# Big-pixel-display-shield.net
KiCad netlist of a schematic drawn in EAGLE
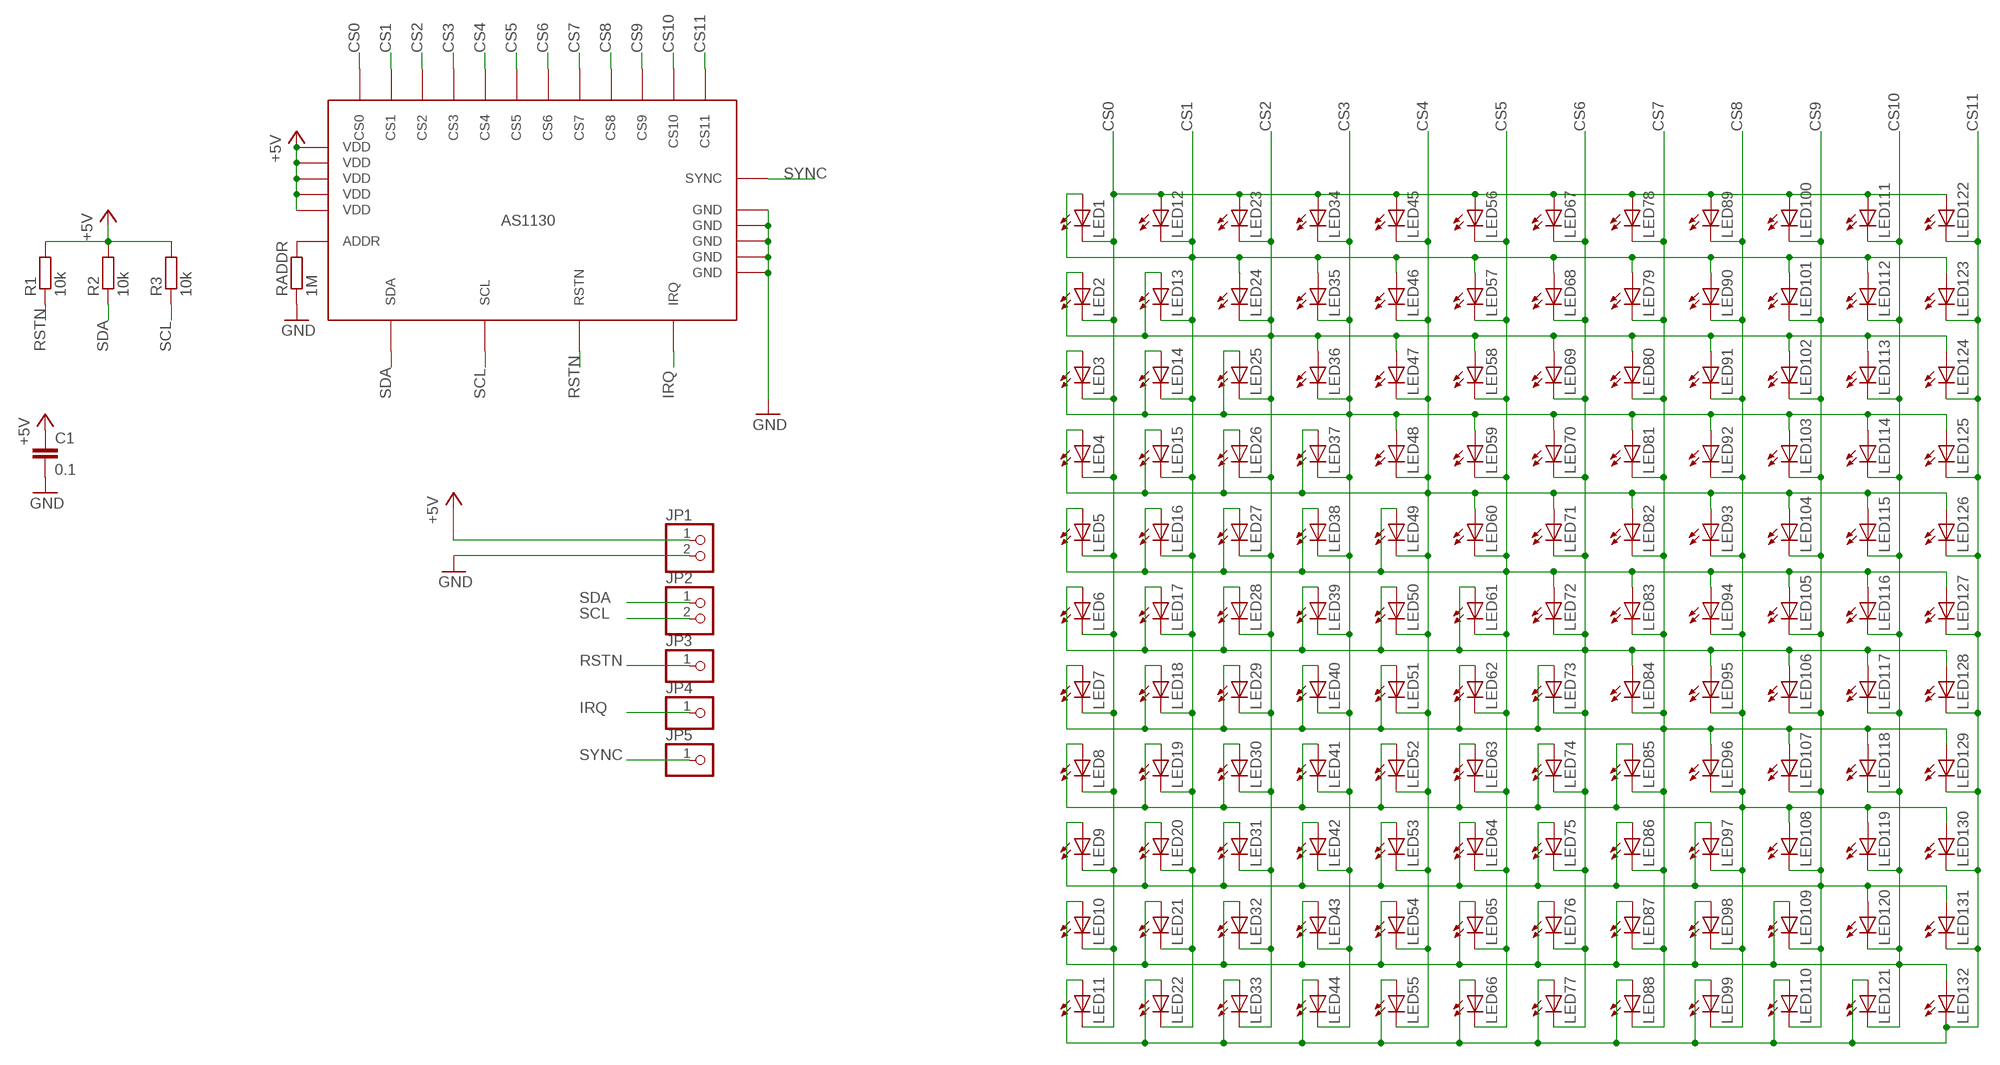
[diagram p0: schematic, sheet 1]

(export (version "E")
  (design (tool "Eeschema 10.0.6"))
  (components
    (comp (ref "C1")
      (value "0.1")
      (footprint "eagle-import:C0805")
      (libsource (lib "eagle-import") (part "C-EUC0805"))
    )
    (comp (ref "JP1")
      (value "PINHD-1X2")
      (footprint "eagle-import:1X02")
      (libsource (lib "eagle-import") (part "PINHD-1X2"))
    )
    (comp (ref "JP2")
      (value "PINHD-1X2")
      (footprint "eagle-import:1X02")
      (libsource (lib "eagle-import") (part "PINHD-1X2"))
    )
    (comp (ref "JP3")
      (value "PINHD-1X1")
      (footprint "eagle-import:1X01")
      (libsource (lib "eagle-import") (part "PINHD-1X1"))
    )
    (comp (ref "JP4")
      (value "PINHD-1X1")
      (footprint "eagle-import:1X01")
      (libsource (lib "eagle-import") (part "PINHD-1X1"))
    )
    (comp (ref "JP5")
      (value "PINHD-1X1")
      (footprint "eagle-import:1X01")
      (libsource (lib "eagle-import") (part "PINHD-1X1"))
    )
    (comp (ref "LED1")
      (value "LED5MM")
      (footprint "eagle-import:LED5MM")
      (libsource (lib "eagle-import") (part "LED5MM"))
    )
    (comp (ref "LED2")
      (value "LED5MM")
      (footprint "eagle-import:LED5MM")
      (libsource (lib "eagle-import") (part "LED5MM"))
    )
    (comp (ref "LED3")
      (value "LED5MM")
      (footprint "eagle-import:LED5MM")
      (libsource (lib "eagle-import") (part "LED5MM"))
    )
    (comp (ref "LED4")
      (value "LED5MM")
      (footprint "eagle-import:LED5MM")
      (libsource (lib "eagle-import") (part "LED5MM"))
    )
    (comp (ref "LED5")
      (value "LED5MM")
      (footprint "eagle-import:LED5MM")
      (libsource (lib "eagle-import") (part "LED5MM"))
    )
    (comp (ref "LED6")
      (value "LED5MM")
      (footprint "eagle-import:LED5MM")
      (libsource (lib "eagle-import") (part "LED5MM"))
    )
    (comp (ref "LED7")
      (value "LED5MM")
      (footprint "eagle-import:LED5MM")
      (libsource (lib "eagle-import") (part "LED5MM"))
    )
    (comp (ref "LED8")
      (value "LED5MM")
      (footprint "eagle-import:LED5MM")
      (libsource (lib "eagle-import") (part "LED5MM"))
    )
    (comp (ref "LED9")
      (value "LED5MM")
      (footprint "eagle-import:LED5MM")
      (libsource (lib "eagle-import") (part "LED5MM"))
    )
    (comp (ref "LED10")
      (value "LED5MM")
      (footprint "eagle-import:LED5MM")
      (libsource (lib "eagle-import") (part "LED5MM"))
    )
    (comp (ref "LED11")
      (value "LED5MM")
      (footprint "eagle-import:LED5MM")
      (libsource (lib "eagle-import") (part "LED5MM"))
    )
    (comp (ref "LED12")
      (value "LED5MM")
      (footprint "eagle-import:LED5MM")
      (libsource (lib "eagle-import") (part "LED5MM"))
    )
    (comp (ref "LED13")
      (value "LED5MM")
      (footprint "eagle-import:LED5MM")
      (libsource (lib "eagle-import") (part "LED5MM"))
    )
    (comp (ref "LED14")
      (value "LED5MM")
      (footprint "eagle-import:LED5MM")
      (libsource (lib "eagle-import") (part "LED5MM"))
    )
    (comp (ref "LED15")
      (value "LED5MM")
      (footprint "eagle-import:LED5MM")
      (libsource (lib "eagle-import") (part "LED5MM"))
    )
    (comp (ref "LED16")
      (value "LED5MM")
      (footprint "eagle-import:LED5MM")
      (libsource (lib "eagle-import") (part "LED5MM"))
    )
    (comp (ref "LED17")
      (value "LED5MM")
      (footprint "eagle-import:LED5MM")
      (libsource (lib "eagle-import") (part "LED5MM"))
    )
    (comp (ref "LED18")
      (value "LED5MM")
      (footprint "eagle-import:LED5MM")
      (libsource (lib "eagle-import") (part "LED5MM"))
    )
    (comp (ref "LED19")
      (value "LED5MM")
      (footprint "eagle-import:LED5MM")
      (libsource (lib "eagle-import") (part "LED5MM"))
    )
    (comp (ref "LED20")
      (value "LED5MM")
      (footprint "eagle-import:LED5MM")
      (libsource (lib "eagle-import") (part "LED5MM"))
    )
    (comp (ref "LED21")
      (value "LED5MM")
      (footprint "eagle-import:LED5MM")
      (libsource (lib "eagle-import") (part "LED5MM"))
    )
    (comp (ref "LED22")
      (value "LED5MM")
      (footprint "eagle-import:LED5MM")
      (libsource (lib "eagle-import") (part "LED5MM"))
    )
    (comp (ref "LED23")
      (value "LED5MM")
      (footprint "eagle-import:LED5MM")
      (libsource (lib "eagle-import") (part "LED5MM"))
    )
    (comp (ref "LED24")
      (value "LED5MM")
      (footprint "eagle-import:LED5MM")
      (libsource (lib "eagle-import") (part "LED5MM"))
    )
    (comp (ref "LED25")
      (value "LED5MM")
      (footprint "eagle-import:LED5MM")
      (libsource (lib "eagle-import") (part "LED5MM"))
    )
    (comp (ref "LED26")
      (value "LED5MM")
      (footprint "eagle-import:LED5MM")
      (libsource (lib "eagle-import") (part "LED5MM"))
    )
    (comp (ref "LED27")
      (value "LED5MM")
      (footprint "eagle-import:LED5MM")
      (libsource (lib "eagle-import") (part "LED5MM"))
    )
    (comp (ref "LED28")
      (value "LED5MM")
      (footprint "eagle-import:LED5MM")
      (libsource (lib "eagle-import") (part "LED5MM"))
    )
    (comp (ref "LED29")
      (value "LED5MM")
      (footprint "eagle-import:LED5MM")
      (libsource (lib "eagle-import") (part "LED5MM"))
    )
    (comp (ref "LED30")
      (value "LED5MM")
      (footprint "eagle-import:LED5MM")
      (libsource (lib "eagle-import") (part "LED5MM"))
    )
    (comp (ref "LED31")
      (value "LED5MM")
      (footprint "eagle-import:LED5MM")
      (libsource (lib "eagle-import") (part "LED5MM"))
    )
    (comp (ref "LED32")
      (value "LED5MM")
      (footprint "eagle-import:LED5MM")
      (libsource (lib "eagle-import") (part "LED5MM"))
    )
    (comp (ref "LED33")
      (value "LED5MM")
      (footprint "eagle-import:LED5MM")
      (libsource (lib "eagle-import") (part "LED5MM"))
    )
    (comp (ref "LED34")
      (value "LED5MM")
      (footprint "eagle-import:LED5MM")
      (libsource (lib "eagle-import") (part "LED5MM"))
    )
    (comp (ref "LED35")
      (value "LED5MM")
      (footprint "eagle-import:LED5MM")
      (libsource (lib "eagle-import") (part "LED5MM"))
    )
    (comp (ref "LED36")
      (value "LED5MM")
      (footprint "eagle-import:LED5MM")
      (libsource (lib "eagle-import") (part "LED5MM"))
    )
    (comp (ref "LED37")
      (value "LED5MM")
      (footprint "eagle-import:LED5MM")
      (libsource (lib "eagle-import") (part "LED5MM"))
    )
    (comp (ref "LED38")
      (value "LED5MM")
      (footprint "eagle-import:LED5MM")
      (libsource (lib "eagle-import") (part "LED5MM"))
    )
    (comp (ref "LED39")
      (value "LED5MM")
      (footprint "eagle-import:LED5MM")
      (libsource (lib "eagle-import") (part "LED5MM"))
    )
    (comp (ref "LED40")
      (value "LED5MM")
      (footprint "eagle-import:LED5MM")
      (libsource (lib "eagle-import") (part "LED5MM"))
    )
    (comp (ref "LED41")
      (value "LED5MM")
      (footprint "eagle-import:LED5MM")
      (libsource (lib "eagle-import") (part "LED5MM"))
    )
    (comp (ref "LED42")
      (value "LED5MM")
      (footprint "eagle-import:LED5MM")
      (libsource (lib "eagle-import") (part "LED5MM"))
    )
    (comp (ref "LED43")
      (value "LED5MM")
      (footprint "eagle-import:LED5MM")
      (libsource (lib "eagle-import") (part "LED5MM"))
    )
    (comp (ref "LED44")
      (value "LED5MM")
      (footprint "eagle-import:LED5MM")
      (libsource (lib "eagle-import") (part "LED5MM"))
    )
    (comp (ref "LED45")
      (value "LED5MM")
      (footprint "eagle-import:LED5MM")
      (libsource (lib "eagle-import") (part "LED5MM"))
    )
    (comp (ref "LED46")
      (value "LED5MM")
      (footprint "eagle-import:LED5MM")
      (libsource (lib "eagle-import") (part "LED5MM"))
    )
    (comp (ref "LED47")
      (value "LED5MM")
      (footprint "eagle-import:LED5MM")
      (libsource (lib "eagle-import") (part "LED5MM"))
    )
    (comp (ref "LED48")
      (value "LED5MM")
      (footprint "eagle-import:LED5MM")
      (libsource (lib "eagle-import") (part "LED5MM"))
    )
    (comp (ref "LED49")
      (value "LED5MM")
      (footprint "eagle-import:LED5MM")
      (libsource (lib "eagle-import") (part "LED5MM"))
    )
    (comp (ref "LED50")
      (value "LED5MM")
      (footprint "eagle-import:LED5MM")
      (libsource (lib "eagle-import") (part "LED5MM"))
    )
    (comp (ref "LED51")
      (value "LED5MM")
      (footprint "eagle-import:LED5MM")
      (libsource (lib "eagle-import") (part "LED5MM"))
    )
    (comp (ref "LED52")
      (value "LED5MM")
      (footprint "eagle-import:LED5MM")
      (libsource (lib "eagle-import") (part "LED5MM"))
    )
    (comp (ref "LED53")
      (value "LED5MM")
      (footprint "eagle-import:LED5MM")
      (libsource (lib "eagle-import") (part "LED5MM"))
    )
    (comp (ref "LED54")
      (value "LED5MM")
      (footprint "eagle-import:LED5MM")
      (libsource (lib "eagle-import") (part "LED5MM"))
    )
    (comp (ref "LED55")
      (value "LED5MM")
      (footprint "eagle-import:LED5MM")
      (libsource (lib "eagle-import") (part "LED5MM"))
    )
    (comp (ref "LED56")
      (value "LED5MM")
      (footprint "eagle-import:LED5MM")
      (libsource (lib "eagle-import") (part "LED5MM"))
    )
    (comp (ref "LED57")
      (value "LED5MM")
      (footprint "eagle-import:LED5MM")
      (libsource (lib "eagle-import") (part "LED5MM"))
    )
    (comp (ref "LED58")
      (value "LED5MM")
      (footprint "eagle-import:LED5MM")
      (libsource (lib "eagle-import") (part "LED5MM"))
    )
    (comp (ref "LED59")
      (value "LED5MM")
      (footprint "eagle-import:LED5MM")
      (libsource (lib "eagle-import") (part "LED5MM"))
    )
    (comp (ref "LED60")
      (value "LED5MM")
      (footprint "eagle-import:LED5MM")
      (libsource (lib "eagle-import") (part "LED5MM"))
    )
    (comp (ref "LED61")
      (value "LED5MM")
      (footprint "eagle-import:LED5MM")
      (libsource (lib "eagle-import") (part "LED5MM"))
    )
    (comp (ref "LED62")
      (value "LED5MM")
      (footprint "eagle-import:LED5MM")
      (libsource (lib "eagle-import") (part "LED5MM"))
    )
    (comp (ref "LED63")
      (value "LED5MM")
      (footprint "eagle-import:LED5MM")
      (libsource (lib "eagle-import") (part "LED5MM"))
    )
    (comp (ref "LED64")
      (value "LED5MM")
      (footprint "eagle-import:LED5MM")
      (libsource (lib "eagle-import") (part "LED5MM"))
    )
    (comp (ref "LED65")
      (value "LED5MM")
      (footprint "eagle-import:LED5MM")
      (libsource (lib "eagle-import") (part "LED5MM"))
    )
    (comp (ref "LED66")
      (value "LED5MM")
      (footprint "eagle-import:LED5MM")
      (libsource (lib "eagle-import") (part "LED5MM"))
    )
    (comp (ref "LED67")
      (value "LED5MM")
      (footprint "eagle-import:LED5MM")
      (libsource (lib "eagle-import") (part "LED5MM"))
    )
    (comp (ref "LED68")
      (value "LED5MM")
      (footprint "eagle-import:LED5MM")
      (libsource (lib "eagle-import") (part "LED5MM"))
    )
    (comp (ref "LED69")
      (value "LED5MM")
      (footprint "eagle-import:LED5MM")
      (libsource (lib "eagle-import") (part "LED5MM"))
    )
    (comp (ref "LED70")
      (value "LED5MM")
      (footprint "eagle-import:LED5MM")
      (libsource (lib "eagle-import") (part "LED5MM"))
    )
    (comp (ref "LED71")
      (value "LED5MM")
      (footprint "eagle-import:LED5MM")
      (libsource (lib "eagle-import") (part "LED5MM"))
    )
    (comp (ref "LED72")
      (value "LED5MM")
      (footprint "eagle-import:LED5MM")
      (libsource (lib "eagle-import") (part "LED5MM"))
    )
    (comp (ref "LED73")
      (value "LED5MM")
      (footprint "eagle-import:LED5MM")
      (libsource (lib "eagle-import") (part "LED5MM"))
    )
    (comp (ref "LED74")
      (value "LED5MM")
      (footprint "eagle-import:LED5MM")
      (libsource (lib "eagle-import") (part "LED5MM"))
    )
    (comp (ref "LED75")
      (value "LED5MM")
      (footprint "eagle-import:LED5MM")
      (libsource (lib "eagle-import") (part "LED5MM"))
    )
    (comp (ref "LED76")
      (value "LED5MM")
      (footprint "eagle-import:LED5MM")
      (libsource (lib "eagle-import") (part "LED5MM"))
    )
    (comp (ref "LED77")
      (value "LED5MM")
      (footprint "eagle-import:LED5MM")
      (libsource (lib "eagle-import") (part "LED5MM"))
    )
    (comp (ref "LED78")
      (value "LED5MM")
      (footprint "eagle-import:LED5MM")
      (libsource (lib "eagle-import") (part "LED5MM"))
    )
    (comp (ref "LED79")
      (value "LED5MM")
      (footprint "eagle-import:LED5MM")
      (libsource (lib "eagle-import") (part "LED5MM"))
    )
    (comp (ref "LED80")
      (value "LED5MM")
      (footprint "eagle-import:LED5MM")
      (libsource (lib "eagle-import") (part "LED5MM"))
    )
    (comp (ref "LED81")
      (value "LED5MM")
      (footprint "eagle-import:LED5MM")
      (libsource (lib "eagle-import") (part "LED5MM"))
    )
    (comp (ref "LED82")
      (value "LED5MM")
      (footprint "eagle-import:LED5MM")
      (libsource (lib "eagle-import") (part "LED5MM"))
    )
    (comp (ref "LED83")
      (value "LED5MM")
      (footprint "eagle-import:LED5MM")
      (libsource (lib "eagle-import") (part "LED5MM"))
    )
    (comp (ref "LED84")
      (value "LED5MM")
      (footprint "eagle-import:LED5MM")
      (libsource (lib "eagle-import") (part "LED5MM"))
    )
    (comp (ref "LED85")
      (value "LED5MM")
      (footprint "eagle-import:LED5MM")
      (libsource (lib "eagle-import") (part "LED5MM"))
    )
    (comp (ref "LED86")
      (value "LED5MM")
      (footprint "eagle-import:LED5MM")
      (libsource (lib "eagle-import") (part "LED5MM"))
    )
    (comp (ref "LED87")
      (value "LED5MM")
      (footprint "eagle-import:LED5MM")
      (libsource (lib "eagle-import") (part "LED5MM"))
    )
    (comp (ref "LED88")
      (value "LED5MM")
      (footprint "eagle-import:LED5MM")
      (libsource (lib "eagle-import") (part "LED5MM"))
    )
    (comp (ref "LED89")
      (value "LED5MM")
      (footprint "eagle-import:LED5MM")
      (libsource (lib "eagle-import") (part "LED5MM"))
    )
    (comp (ref "LED90")
      (value "LED5MM")
      (footprint "eagle-import:LED5MM")
      (libsource (lib "eagle-import") (part "LED5MM"))
    )
    (comp (ref "LED91")
      (value "LED5MM")
      (footprint "eagle-import:LED5MM")
      (libsource (lib "eagle-import") (part "LED5MM"))
    )
    (comp (ref "LED92")
      (value "LED5MM")
      (footprint "eagle-import:LED5MM")
      (libsource (lib "eagle-import") (part "LED5MM"))
    )
    (comp (ref "LED93")
      (value "LED5MM")
      (footprint "eagle-import:LED5MM")
      (libsource (lib "eagle-import") (part "LED5MM"))
    )
    (comp (ref "LED94")
      (value "LED5MM")
      (footprint "eagle-import:LED5MM")
      (libsource (lib "eagle-import") (part "LED5MM"))
    )
    (comp (ref "LED95")
      (value "LED5MM")
      (footprint "eagle-import:LED5MM")
      (libsource (lib "eagle-import") (part "LED5MM"))
    )
    (comp (ref "LED96")
      (value "LED5MM")
      (footprint "eagle-import:LED5MM")
      (libsource (lib "eagle-import") (part "LED5MM"))
    )
    (comp (ref "LED97")
      (value "LED5MM")
      (footprint "eagle-import:LED5MM")
      (libsource (lib "eagle-import") (part "LED5MM"))
    )
    (comp (ref "LED98")
      (value "LED5MM")
      (footprint "eagle-import:LED5MM")
      (libsource (lib "eagle-import") (part "LED5MM"))
    )
    (comp (ref "LED99")
      (value "LED5MM")
      (footprint "eagle-import:LED5MM")
      (libsource (lib "eagle-import") (part "LED5MM"))
    )
    (comp (ref "LED100")
      (value "LED5MM")
      (footprint "eagle-import:LED5MM")
      (libsource (lib "eagle-import") (part "LED5MM"))
    )
    (comp (ref "LED101")
      (value "LED5MM")
      (footprint "eagle-import:LED5MM")
      (libsource (lib "eagle-import") (part "LED5MM"))
    )
    (comp (ref "LED102")
      (value "LED5MM")
      (footprint "eagle-import:LED5MM")
      (libsource (lib "eagle-import") (part "LED5MM"))
    )
    (comp (ref "LED103")
      (value "LED5MM")
      (footprint "eagle-import:LED5MM")
      (libsource (lib "eagle-import") (part "LED5MM"))
    )
    (comp (ref "LED104")
      (value "LED5MM")
      (footprint "eagle-import:LED5MM")
      (libsource (lib "eagle-import") (part "LED5MM"))
    )
    (comp (ref "LED105")
      (value "LED5MM")
      (footprint "eagle-import:LED5MM")
      (libsource (lib "eagle-import") (part "LED5MM"))
    )
    (comp (ref "LED106")
      (value "LED5MM")
      (footprint "eagle-import:LED5MM")
      (libsource (lib "eagle-import") (part "LED5MM"))
    )
    (comp (ref "LED107")
      (value "LED5MM")
      (footprint "eagle-import:LED5MM")
      (libsource (lib "eagle-import") (part "LED5MM"))
    )
    (comp (ref "LED108")
      (value "LED5MM")
      (footprint "eagle-import:LED5MM")
      (libsource (lib "eagle-import") (part "LED5MM"))
    )
    (comp (ref "LED109")
      (value "LED5MM")
      (footprint "eagle-import:LED5MM")
      (libsource (lib "eagle-import") (part "LED5MM"))
    )
    (comp (ref "LED110")
      (value "LED5MM")
      (footprint "eagle-import:LED5MM")
      (libsource (lib "eagle-import") (part "LED5MM"))
    )
    (comp (ref "LED111")
      (value "LED5MM")
      (footprint "eagle-import:LED5MM")
      (libsource (lib "eagle-import") (part "LED5MM"))
    )
    (comp (ref "LED112")
      (value "LED5MM")
      (footprint "eagle-import:LED5MM")
      (libsource (lib "eagle-import") (part "LED5MM"))
    )
    (comp (ref "LED113")
      (value "LED5MM")
      (footprint "eagle-import:LED5MM")
      (libsource (lib "eagle-import") (part "LED5MM"))
    )
    (comp (ref "LED114")
      (value "LED5MM")
      (footprint "eagle-import:LED5MM")
      (libsource (lib "eagle-import") (part "LED5MM"))
    )
    (comp (ref "LED115")
      (value "LED5MM")
      (footprint "eagle-import:LED5MM")
      (libsource (lib "eagle-import") (part "LED5MM"))
    )
    (comp (ref "LED116")
      (value "LED5MM")
      (footprint "eagle-import:LED5MM")
      (libsource (lib "eagle-import") (part "LED5MM"))
    )
    (comp (ref "LED117")
      (value "LED5MM")
      (footprint "eagle-import:LED5MM")
      (libsource (lib "eagle-import") (part "LED5MM"))
    )
    (comp (ref "LED118")
      (value "LED5MM")
      (footprint "eagle-import:LED5MM")
      (libsource (lib "eagle-import") (part "LED5MM"))
    )
    (comp (ref "LED119")
      (value "LED5MM")
      (footprint "eagle-import:LED5MM")
      (libsource (lib "eagle-import") (part "LED5MM"))
    )
    (comp (ref "LED120")
      (value "LED5MM")
      (footprint "eagle-import:LED5MM")
      (libsource (lib "eagle-import") (part "LED5MM"))
    )
    (comp (ref "LED121")
      (value "LED5MM")
      (footprint "eagle-import:LED5MM")
      (libsource (lib "eagle-import") (part "LED5MM"))
    )
    (comp (ref "LED122")
      (value "LED5MM")
      (footprint "eagle-import:LED5MM")
      (libsource (lib "eagle-import") (part "LED5MM"))
    )
    (comp (ref "LED123")
      (value "LED5MM")
      (footprint "eagle-import:LED5MM")
      (libsource (lib "eagle-import") (part "LED5MM"))
    )
    (comp (ref "LED124")
      (value "LED5MM")
      (footprint "eagle-import:LED5MM")
      (libsource (lib "eagle-import") (part "LED5MM"))
    )
    (comp (ref "LED125")
      (value "LED5MM")
      (footprint "eagle-import:LED5MM")
      (libsource (lib "eagle-import") (part "LED5MM"))
    )
    (comp (ref "LED126")
      (value "LED5MM")
      (footprint "eagle-import:LED5MM")
      (libsource (lib "eagle-import") (part "LED5MM"))
    )
    (comp (ref "LED127")
      (value "LED5MM")
      (footprint "eagle-import:LED5MM")
      (libsource (lib "eagle-import") (part "LED5MM"))
    )
    (comp (ref "LED128")
      (value "LED5MM")
      (footprint "eagle-import:LED5MM")
      (libsource (lib "eagle-import") (part "LED5MM"))
    )
    (comp (ref "LED129")
      (value "LED5MM")
      (footprint "eagle-import:LED5MM")
      (libsource (lib "eagle-import") (part "LED5MM"))
    )
    (comp (ref "LED130")
      (value "LED5MM")
      (footprint "eagle-import:LED5MM")
      (libsource (lib "eagle-import") (part "LED5MM"))
    )
    (comp (ref "LED131")
      (value "LED5MM")
      (footprint "eagle-import:LED5MM")
      (libsource (lib "eagle-import") (part "LED5MM"))
    )
    (comp (ref "LED132")
      (value "LED5MM")
      (footprint "eagle-import:LED5MM")
      (libsource (lib "eagle-import") (part "LED5MM"))
    )
    (comp (ref "R1")
      (value "10k")
      (footprint "eagle-import:R1206")
      (libsource (lib "eagle-import") (part "R-EU_R1206"))
    )
    (comp (ref "R2")
      (value "10k")
      (footprint "eagle-import:R1206")
      (libsource (lib "eagle-import") (part "R-EU_R1206"))
    )
    (comp (ref "R3")
      (value "10k")
      (footprint "eagle-import:R1206")
      (libsource (lib "eagle-import") (part "R-EU_R1206"))
    )
    (comp (ref "RADDR")
      (value "1M")
      (footprint "eagle-import:R1206")
      (libsource (lib "eagle-import") (part "R-EU_R1206"))
    )
    (comp (ref "U$1")
      (value "AS1130")
      (footprint "eagle-import:SSOP28")
      (libsource (lib "eagle-import") (part "AS1130"))
    )
  )
  (nets
    (net (code "1") (name "+5V") (class "Default")
      (node (ref "C1") (pin "1") (pinfunction "1_1") (pintype "passive"))
      (node (ref "JP1") (pin "1") (pinfunction "1_1") (pintype "passive"))
      (node (ref "R1") (pin "2") (pinfunction "2_2") (pintype "passive"))
      (node (ref "R2") (pin "2") (pinfunction "2_2") (pintype "passive"))
      (node (ref "R3") (pin "2") (pinfunction "2_2") (pintype "passive"))
      (node (ref "U$1") (pin "10") (pinfunction "VDD_10") (pintype "bidirectional"))
      (node (ref "U$1") (pin "18") (pinfunction "VDD_18") (pintype "bidirectional"))
      (node (ref "U$1") (pin "19") (pinfunction "VDD_19") (pintype "bidirectional"))
      (node (ref "U$1") (pin "26") (pinfunction "VDD_26") (pintype "bidirectional"))
      (node (ref "U$1") (pin "3") (pinfunction "VDD_3") (pintype "bidirectional"))
    )
    (net (code "2") (name "/CS0") (class "Default")
      (node (ref "LED1") (pin "K") (pinfunction "C_K") (pintype "passive"))
      (node (ref "LED10") (pin "K") (pinfunction "C_K") (pintype "passive"))
      (node (ref "LED100") (pin "A") (pinfunction "A_A") (pintype "passive"))
      (node (ref "LED11") (pin "K") (pinfunction "C_K") (pintype "passive"))
      (node (ref "LED111") (pin "A") (pinfunction "A_A") (pintype "passive"))
      (node (ref "LED12") (pin "A") (pinfunction "A_A") (pintype "passive"))
      (node (ref "LED122") (pin "A") (pinfunction "A_A") (pintype "passive"))
      (node (ref "LED2") (pin "K") (pinfunction "C_K") (pintype "passive"))
      (node (ref "LED23") (pin "A") (pinfunction "A_A") (pintype "passive"))
      (node (ref "LED3") (pin "K") (pinfunction "C_K") (pintype "passive"))
      (node (ref "LED34") (pin "A") (pinfunction "A_A") (pintype "passive"))
      (node (ref "LED4") (pin "K") (pinfunction "C_K") (pintype "passive"))
      (node (ref "LED45") (pin "A") (pinfunction "A_A") (pintype "passive"))
      (node (ref "LED5") (pin "K") (pinfunction "C_K") (pintype "passive"))
      (node (ref "LED56") (pin "A") (pinfunction "A_A") (pintype "passive"))
      (node (ref "LED6") (pin "K") (pinfunction "C_K") (pintype "passive"))
      (node (ref "LED67") (pin "A") (pinfunction "A_A") (pintype "passive"))
      (node (ref "LED7") (pin "K") (pinfunction "C_K") (pintype "passive"))
      (node (ref "LED78") (pin "A") (pinfunction "A_A") (pintype "passive"))
      (node (ref "LED8") (pin "K") (pinfunction "C_K") (pintype "passive"))
      (node (ref "LED89") (pin "A") (pinfunction "A_A") (pintype "passive"))
      (node (ref "LED9") (pin "K") (pinfunction "C_K") (pintype "passive"))
      (node (ref "U$1") (pin "25") (pinfunction "CS0_25") (pintype "bidirectional"))
    )
    (net (code "3") (name "/CS1") (class "Default")
      (node (ref "LED1") (pin "A") (pinfunction "A_A") (pintype "passive"))
      (node (ref "LED101") (pin "A") (pinfunction "A_A") (pintype "passive"))
      (node (ref "LED112") (pin "A") (pinfunction "A_A") (pintype "passive"))
      (node (ref "LED12") (pin "K") (pinfunction "C_K") (pintype "passive"))
      (node (ref "LED123") (pin "A") (pinfunction "A_A") (pintype "passive"))
      (node (ref "LED13") (pin "K") (pinfunction "C_K") (pintype "passive"))
      (node (ref "LED14") (pin "K") (pinfunction "C_K") (pintype "passive"))
      (node (ref "LED15") (pin "K") (pinfunction "C_K") (pintype "passive"))
      (node (ref "LED16") (pin "K") (pinfunction "C_K") (pintype "passive"))
      (node (ref "LED17") (pin "K") (pinfunction "C_K") (pintype "passive"))
      (node (ref "LED18") (pin "K") (pinfunction "C_K") (pintype "passive"))
      (node (ref "LED19") (pin "K") (pinfunction "C_K") (pintype "passive"))
      (node (ref "LED20") (pin "K") (pinfunction "C_K") (pintype "passive"))
      (node (ref "LED21") (pin "K") (pinfunction "C_K") (pintype "passive"))
      (node (ref "LED22") (pin "K") (pinfunction "C_K") (pintype "passive"))
      (node (ref "LED24") (pin "A") (pinfunction "A_A") (pintype "passive"))
      (node (ref "LED35") (pin "A") (pinfunction "A_A") (pintype "passive"))
      (node (ref "LED46") (pin "A") (pinfunction "A_A") (pintype "passive"))
      (node (ref "LED57") (pin "A") (pinfunction "A_A") (pintype "passive"))
      (node (ref "LED68") (pin "A") (pinfunction "A_A") (pintype "passive"))
      (node (ref "LED79") (pin "A") (pinfunction "A_A") (pintype "passive"))
      (node (ref "LED90") (pin "A") (pinfunction "A_A") (pintype "passive"))
      (node (ref "U$1") (pin "27") (pinfunction "CS1_27") (pintype "bidirectional"))
    )
    (net (code "4") (name "/CS2") (class "Default")
      (node (ref "LED102") (pin "A") (pinfunction "A_A") (pintype "passive"))
      (node (ref "LED113") (pin "A") (pinfunction "A_A") (pintype "passive"))
      (node (ref "LED124") (pin "A") (pinfunction "A_A") (pintype "passive"))
      (node (ref "LED13") (pin "A") (pinfunction "A_A") (pintype "passive"))
      (node (ref "LED2") (pin "A") (pinfunction "A_A") (pintype "passive"))
      (node (ref "LED23") (pin "K") (pinfunction "C_K") (pintype "passive"))
      (node (ref "LED24") (pin "K") (pinfunction "C_K") (pintype "passive"))
      (node (ref "LED25") (pin "K") (pinfunction "C_K") (pintype "passive"))
      (node (ref "LED26") (pin "K") (pinfunction "C_K") (pintype "passive"))
      (node (ref "LED27") (pin "K") (pinfunction "C_K") (pintype "passive"))
      (node (ref "LED28") (pin "K") (pinfunction "C_K") (pintype "passive"))
      (node (ref "LED29") (pin "K") (pinfunction "C_K") (pintype "passive"))
      (node (ref "LED30") (pin "K") (pinfunction "C_K") (pintype "passive"))
      (node (ref "LED31") (pin "K") (pinfunction "C_K") (pintype "passive"))
      (node (ref "LED32") (pin "K") (pinfunction "C_K") (pintype "passive"))
      (node (ref "LED33") (pin "K") (pinfunction "C_K") (pintype "passive"))
      (node (ref "LED36") (pin "A") (pinfunction "A_A") (pintype "passive"))
      (node (ref "LED47") (pin "A") (pinfunction "A_A") (pintype "passive"))
      (node (ref "LED58") (pin "A") (pinfunction "A_A") (pintype "passive"))
      (node (ref "LED69") (pin "A") (pinfunction "A_A") (pintype "passive"))
      (node (ref "LED80") (pin "A") (pinfunction "A_A") (pintype "passive"))
      (node (ref "LED91") (pin "A") (pinfunction "A_A") (pintype "passive"))
      (node (ref "U$1") (pin "23") (pinfunction "CS2_23") (pintype "bidirectional"))
    )
    (net (code "5") (name "/CS3") (class "Default")
      (node (ref "LED103") (pin "A") (pinfunction "A_A") (pintype "passive"))
      (node (ref "LED114") (pin "A") (pinfunction "A_A") (pintype "passive"))
      (node (ref "LED125") (pin "A") (pinfunction "A_A") (pintype "passive"))
      (node (ref "LED14") (pin "A") (pinfunction "A_A") (pintype "passive"))
      (node (ref "LED25") (pin "A") (pinfunction "A_A") (pintype "passive"))
      (node (ref "LED3") (pin "A") (pinfunction "A_A") (pintype "passive"))
      (node (ref "LED34") (pin "K") (pinfunction "C_K") (pintype "passive"))
      (node (ref "LED35") (pin "K") (pinfunction "C_K") (pintype "passive"))
      (node (ref "LED36") (pin "K") (pinfunction "C_K") (pintype "passive"))
      (node (ref "LED37") (pin "K") (pinfunction "C_K") (pintype "passive"))
      (node (ref "LED38") (pin "K") (pinfunction "C_K") (pintype "passive"))
      (node (ref "LED39") (pin "K") (pinfunction "C_K") (pintype "passive"))
      (node (ref "LED40") (pin "K") (pinfunction "C_K") (pintype "passive"))
      (node (ref "LED41") (pin "K") (pinfunction "C_K") (pintype "passive"))
      (node (ref "LED42") (pin "K") (pinfunction "C_K") (pintype "passive"))
      (node (ref "LED43") (pin "K") (pinfunction "C_K") (pintype "passive"))
      (node (ref "LED44") (pin "K") (pinfunction "C_K") (pintype "passive"))
      (node (ref "LED48") (pin "A") (pinfunction "A_A") (pintype "passive"))
      (node (ref "LED59") (pin "A") (pinfunction "A_A") (pintype "passive"))
      (node (ref "LED70") (pin "A") (pinfunction "A_A") (pintype "passive"))
      (node (ref "LED81") (pin "A") (pinfunction "A_A") (pintype "passive"))
      (node (ref "LED92") (pin "A") (pinfunction "A_A") (pintype "passive"))
      (node (ref "U$1") (pin "24") (pinfunction "CS3_24") (pintype "bidirectional"))
    )
    (net (code "6") (name "/CS4") (class "Default")
      (node (ref "LED104") (pin "A") (pinfunction "A_A") (pintype "passive"))
      (node (ref "LED115") (pin "A") (pinfunction "A_A") (pintype "passive"))
      (node (ref "LED126") (pin "A") (pinfunction "A_A") (pintype "passive"))
      (node (ref "LED15") (pin "A") (pinfunction "A_A") (pintype "passive"))
      (node (ref "LED26") (pin "A") (pinfunction "A_A") (pintype "passive"))
      (node (ref "LED37") (pin "A") (pinfunction "A_A") (pintype "passive"))
      (node (ref "LED4") (pin "A") (pinfunction "A_A") (pintype "passive"))
      (node (ref "LED45") (pin "K") (pinfunction "C_K") (pintype "passive"))
      (node (ref "LED46") (pin "K") (pinfunction "C_K") (pintype "passive"))
      (node (ref "LED47") (pin "K") (pinfunction "C_K") (pintype "passive"))
      (node (ref "LED48") (pin "K") (pinfunction "C_K") (pintype "passive"))
      (node (ref "LED49") (pin "K") (pinfunction "C_K") (pintype "passive"))
      (node (ref "LED50") (pin "K") (pinfunction "C_K") (pintype "passive"))
      (node (ref "LED51") (pin "K") (pinfunction "C_K") (pintype "passive"))
      (node (ref "LED52") (pin "K") (pinfunction "C_K") (pintype "passive"))
      (node (ref "LED53") (pin "K") (pinfunction "C_K") (pintype "passive"))
      (node (ref "LED54") (pin "K") (pinfunction "C_K") (pintype "passive"))
      (node (ref "LED55") (pin "K") (pinfunction "C_K") (pintype "passive"))
      (node (ref "LED60") (pin "A") (pinfunction "A_A") (pintype "passive"))
      (node (ref "LED71") (pin "A") (pinfunction "A_A") (pintype "passive"))
      (node (ref "LED82") (pin "A") (pinfunction "A_A") (pintype "passive"))
      (node (ref "LED93") (pin "A") (pinfunction "A_A") (pintype "passive"))
      (node (ref "U$1") (pin "21") (pinfunction "CS4_21") (pintype "bidirectional"))
    )
    (net (code "7") (name "/CS5") (class "Default")
      (node (ref "LED105") (pin "A") (pinfunction "A_A") (pintype "passive"))
      (node (ref "LED116") (pin "A") (pinfunction "A_A") (pintype "passive"))
      (node (ref "LED127") (pin "A") (pinfunction "A_A") (pintype "passive"))
      (node (ref "LED16") (pin "A") (pinfunction "A_A") (pintype "passive"))
      (node (ref "LED27") (pin "A") (pinfunction "A_A") (pintype "passive"))
      (node (ref "LED38") (pin "A") (pinfunction "A_A") (pintype "passive"))
      (node (ref "LED49") (pin "A") (pinfunction "A_A") (pintype "passive"))
      (node (ref "LED5") (pin "A") (pinfunction "A_A") (pintype "passive"))
      (node (ref "LED56") (pin "K") (pinfunction "C_K") (pintype "passive"))
      (node (ref "LED57") (pin "K") (pinfunction "C_K") (pintype "passive"))
      (node (ref "LED58") (pin "K") (pinfunction "C_K") (pintype "passive"))
      (node (ref "LED59") (pin "K") (pinfunction "C_K") (pintype "passive"))
      (node (ref "LED60") (pin "K") (pinfunction "C_K") (pintype "passive"))
      (node (ref "LED61") (pin "K") (pinfunction "C_K") (pintype "passive"))
      (node (ref "LED62") (pin "K") (pinfunction "C_K") (pintype "passive"))
      (node (ref "LED63") (pin "K") (pinfunction "C_K") (pintype "passive"))
      (node (ref "LED64") (pin "K") (pinfunction "C_K") (pintype "passive"))
      (node (ref "LED65") (pin "K") (pinfunction "C_K") (pintype "passive"))
      (node (ref "LED66") (pin "K") (pinfunction "C_K") (pintype "passive"))
      (node (ref "LED72") (pin "A") (pinfunction "A_A") (pintype "passive"))
      (node (ref "LED83") (pin "A") (pinfunction "A_A") (pintype "passive"))
      (node (ref "LED94") (pin "A") (pinfunction "A_A") (pintype "passive"))
      (node (ref "U$1") (pin "20") (pinfunction "CS5_20") (pintype "bidirectional"))
    )
    (net (code "8") (name "/CS6") (class "Default")
      (node (ref "LED106") (pin "A") (pinfunction "A_A") (pintype "passive"))
      (node (ref "LED117") (pin "A") (pinfunction "A_A") (pintype "passive"))
      (node (ref "LED128") (pin "A") (pinfunction "A_A") (pintype "passive"))
      (node (ref "LED17") (pin "A") (pinfunction "A_A") (pintype "passive"))
      (node (ref "LED28") (pin "A") (pinfunction "A_A") (pintype "passive"))
      (node (ref "LED39") (pin "A") (pinfunction "A_A") (pintype "passive"))
      (node (ref "LED50") (pin "A") (pinfunction "A_A") (pintype "passive"))
      (node (ref "LED6") (pin "A") (pinfunction "A_A") (pintype "passive"))
      (node (ref "LED61") (pin "A") (pinfunction "A_A") (pintype "passive"))
      (node (ref "LED67") (pin "K") (pinfunction "C_K") (pintype "passive"))
      (node (ref "LED68") (pin "K") (pinfunction "C_K") (pintype "passive"))
      (node (ref "LED69") (pin "K") (pinfunction "C_K") (pintype "passive"))
      (node (ref "LED70") (pin "K") (pinfunction "C_K") (pintype "passive"))
      (node (ref "LED71") (pin "K") (pinfunction "C_K") (pintype "passive"))
      (node (ref "LED72") (pin "K") (pinfunction "C_K") (pintype "passive"))
      (node (ref "LED73") (pin "K") (pinfunction "C_K") (pintype "passive"))
      (node (ref "LED74") (pin "K") (pinfunction "C_K") (pintype "passive"))
      (node (ref "LED75") (pin "K") (pinfunction "C_K") (pintype "passive"))
      (node (ref "LED76") (pin "K") (pinfunction "C_K") (pintype "passive"))
      (node (ref "LED77") (pin "K") (pinfunction "C_K") (pintype "passive"))
      (node (ref "LED84") (pin "A") (pinfunction "A_A") (pintype "passive"))
      (node (ref "LED95") (pin "A") (pinfunction "A_A") (pintype "passive"))
      (node (ref "U$1") (pin "2") (pinfunction "CS6_2") (pintype "bidirectional"))
    )
    (net (code "9") (name "/CS7") (class "Default")
      (node (ref "LED107") (pin "A") (pinfunction "A_A") (pintype "passive"))
      (node (ref "LED118") (pin "A") (pinfunction "A_A") (pintype "passive"))
      (node (ref "LED129") (pin "A") (pinfunction "A_A") (pintype "passive"))
      (node (ref "LED18") (pin "A") (pinfunction "A_A") (pintype "passive"))
      (node (ref "LED29") (pin "A") (pinfunction "A_A") (pintype "passive"))
      (node (ref "LED40") (pin "A") (pinfunction "A_A") (pintype "passive"))
      (node (ref "LED51") (pin "A") (pinfunction "A_A") (pintype "passive"))
      (node (ref "LED62") (pin "A") (pinfunction "A_A") (pintype "passive"))
      (node (ref "LED7") (pin "A") (pinfunction "A_A") (pintype "passive"))
      (node (ref "LED73") (pin "A") (pinfunction "A_A") (pintype "passive"))
      (node (ref "LED78") (pin "K") (pinfunction "C_K") (pintype "passive"))
      (node (ref "LED79") (pin "K") (pinfunction "C_K") (pintype "passive"))
      (node (ref "LED80") (pin "K") (pinfunction "C_K") (pintype "passive"))
      (node (ref "LED81") (pin "K") (pinfunction "C_K") (pintype "passive"))
      (node (ref "LED82") (pin "K") (pinfunction "C_K") (pintype "passive"))
      (node (ref "LED83") (pin "K") (pinfunction "C_K") (pintype "passive"))
      (node (ref "LED84") (pin "K") (pinfunction "C_K") (pintype "passive"))
      (node (ref "LED85") (pin "K") (pinfunction "C_K") (pintype "passive"))
      (node (ref "LED86") (pin "K") (pinfunction "C_K") (pintype "passive"))
      (node (ref "LED87") (pin "K") (pinfunction "C_K") (pintype "passive"))
      (node (ref "LED88") (pin "K") (pinfunction "C_K") (pintype "passive"))
      (node (ref "LED96") (pin "A") (pinfunction "A_A") (pintype "passive"))
      (node (ref "U$1") (pin "4") (pinfunction "CS7_4") (pintype "bidirectional"))
    )
    (net (code "10") (name "/CS8") (class "Default")
      (node (ref "LED108") (pin "A") (pinfunction "A_A") (pintype "passive"))
      (node (ref "LED119") (pin "A") (pinfunction "A_A") (pintype "passive"))
      (node (ref "LED130") (pin "A") (pinfunction "A_A") (pintype "passive"))
      (node (ref "LED19") (pin "A") (pinfunction "A_A") (pintype "passive"))
      (node (ref "LED30") (pin "A") (pinfunction "A_A") (pintype "passive"))
      (node (ref "LED41") (pin "A") (pinfunction "A_A") (pintype "passive"))
      (node (ref "LED52") (pin "A") (pinfunction "A_A") (pintype "passive"))
      (node (ref "LED63") (pin "A") (pinfunction "A_A") (pintype "passive"))
      (node (ref "LED74") (pin "A") (pinfunction "A_A") (pintype "passive"))
      (node (ref "LED8") (pin "A") (pinfunction "A_A") (pintype "passive"))
      (node (ref "LED85") (pin "A") (pinfunction "A_A") (pintype "passive"))
      (node (ref "LED89") (pin "K") (pinfunction "C_K") (pintype "passive"))
      (node (ref "LED90") (pin "K") (pinfunction "C_K") (pintype "passive"))
      (node (ref "LED91") (pin "K") (pinfunction "C_K") (pintype "passive"))
      (node (ref "LED92") (pin "K") (pinfunction "C_K") (pintype "passive"))
      (node (ref "LED93") (pin "K") (pinfunction "C_K") (pintype "passive"))
      (node (ref "LED94") (pin "K") (pinfunction "C_K") (pintype "passive"))
      (node (ref "LED95") (pin "K") (pinfunction "C_K") (pintype "passive"))
      (node (ref "LED96") (pin "K") (pinfunction "C_K") (pintype "passive"))
      (node (ref "LED97") (pin "K") (pinfunction "C_K") (pintype "passive"))
      (node (ref "LED98") (pin "K") (pinfunction "C_K") (pintype "passive"))
      (node (ref "LED99") (pin "K") (pinfunction "C_K") (pintype "passive"))
      (node (ref "U$1") (pin "5") (pinfunction "CS8_5") (pintype "bidirectional"))
    )
    (net (code "11") (name "/CS9") (class "Default")
      (node (ref "LED100") (pin "K") (pinfunction "C_K") (pintype "passive"))
      (node (ref "LED101") (pin "K") (pinfunction "C_K") (pintype "passive"))
      (node (ref "LED102") (pin "K") (pinfunction "C_K") (pintype "passive"))
      (node (ref "LED103") (pin "K") (pinfunction "C_K") (pintype "passive"))
      (node (ref "LED104") (pin "K") (pinfunction "C_K") (pintype "passive"))
      (node (ref "LED105") (pin "K") (pinfunction "C_K") (pintype "passive"))
      (node (ref "LED106") (pin "K") (pinfunction "C_K") (pintype "passive"))
      (node (ref "LED107") (pin "K") (pinfunction "C_K") (pintype "passive"))
      (node (ref "LED108") (pin "K") (pinfunction "C_K") (pintype "passive"))
      (node (ref "LED109") (pin "K") (pinfunction "C_K") (pintype "passive"))
      (node (ref "LED110") (pin "K") (pinfunction "C_K") (pintype "passive"))
      (node (ref "LED120") (pin "A") (pinfunction "A_A") (pintype "passive"))
      (node (ref "LED131") (pin "A") (pinfunction "A_A") (pintype "passive"))
      (node (ref "LED20") (pin "A") (pinfunction "A_A") (pintype "passive"))
      (node (ref "LED31") (pin "A") (pinfunction "A_A") (pintype "passive"))
      (node (ref "LED42") (pin "A") (pinfunction "A_A") (pintype "passive"))
      (node (ref "LED53") (pin "A") (pinfunction "A_A") (pintype "passive"))
      (node (ref "LED64") (pin "A") (pinfunction "A_A") (pintype "passive"))
      (node (ref "LED75") (pin "A") (pinfunction "A_A") (pintype "passive"))
      (node (ref "LED86") (pin "A") (pinfunction "A_A") (pintype "passive"))
      (node (ref "LED9") (pin "A") (pinfunction "A_A") (pintype "passive"))
      (node (ref "LED97") (pin "A") (pinfunction "A_A") (pintype "passive"))
      (node (ref "U$1") (pin "6") (pinfunction "CS9_6") (pintype "bidirectional"))
    )
    (net (code "12") (name "/CS10") (class "Default")
      (node (ref "LED10") (pin "A") (pinfunction "A_A") (pintype "passive"))
      (node (ref "LED109") (pin "A") (pinfunction "A_A") (pintype "passive"))
      (node (ref "LED111") (pin "K") (pinfunction "C_K") (pintype "passive"))
      (node (ref "LED112") (pin "K") (pinfunction "C_K") (pintype "passive"))
      (node (ref "LED113") (pin "K") (pinfunction "C_K") (pintype "passive"))
      (node (ref "LED114") (pin "K") (pinfunction "C_K") (pintype "passive"))
      (node (ref "LED115") (pin "K") (pinfunction "C_K") (pintype "passive"))
      (node (ref "LED116") (pin "K") (pinfunction "C_K") (pintype "passive"))
      (node (ref "LED117") (pin "K") (pinfunction "C_K") (pintype "passive"))
      (node (ref "LED118") (pin "K") (pinfunction "C_K") (pintype "passive"))
      (node (ref "LED119") (pin "K") (pinfunction "C_K") (pintype "passive"))
      (node (ref "LED120") (pin "K") (pinfunction "C_K") (pintype "passive"))
      (node (ref "LED121") (pin "K") (pinfunction "C_K") (pintype "passive"))
      (node (ref "LED132") (pin "A") (pinfunction "A_A") (pintype "passive"))
      (node (ref "LED21") (pin "A") (pinfunction "A_A") (pintype "passive"))
      (node (ref "LED32") (pin "A") (pinfunction "A_A") (pintype "passive"))
      (node (ref "LED43") (pin "A") (pinfunction "A_A") (pintype "passive"))
      (node (ref "LED54") (pin "A") (pinfunction "A_A") (pintype "passive"))
      (node (ref "LED65") (pin "A") (pinfunction "A_A") (pintype "passive"))
      (node (ref "LED76") (pin "A") (pinfunction "A_A") (pintype "passive"))
      (node (ref "LED87") (pin "A") (pinfunction "A_A") (pintype "passive"))
      (node (ref "LED98") (pin "A") (pinfunction "A_A") (pintype "passive"))
      (node (ref "U$1") (pin "9") (pinfunction "CS10_9") (pintype "bidirectional"))
    )
    (net (code "13") (name "/CS11") (class "Default")
      (node (ref "LED11") (pin "A") (pinfunction "A_A") (pintype "passive"))
      (node (ref "LED110") (pin "A") (pinfunction "A_A") (pintype "passive"))
      (node (ref "LED121") (pin "A") (pinfunction "A_A") (pintype "passive"))
      (node (ref "LED122") (pin "K") (pinfunction "C_K") (pintype "passive"))
      (node (ref "LED123") (pin "K") (pinfunction "C_K") (pintype "passive"))
      (node (ref "LED124") (pin "K") (pinfunction "C_K") (pintype "passive"))
      (node (ref "LED125") (pin "K") (pinfunction "C_K") (pintype "passive"))
      (node (ref "LED126") (pin "K") (pinfunction "C_K") (pintype "passive"))
      (node (ref "LED127") (pin "K") (pinfunction "C_K") (pintype "passive"))
      (node (ref "LED128") (pin "K") (pinfunction "C_K") (pintype "passive"))
      (node (ref "LED129") (pin "K") (pinfunction "C_K") (pintype "passive"))
      (node (ref "LED130") (pin "K") (pinfunction "C_K") (pintype "passive"))
      (node (ref "LED131") (pin "K") (pinfunction "C_K") (pintype "passive"))
      (node (ref "LED132") (pin "K") (pinfunction "C_K") (pintype "passive"))
      (node (ref "LED22") (pin "A") (pinfunction "A_A") (pintype "passive"))
      (node (ref "LED33") (pin "A") (pinfunction "A_A") (pintype "passive"))
      (node (ref "LED44") (pin "A") (pinfunction "A_A") (pintype "passive"))
      (node (ref "LED55") (pin "A") (pinfunction "A_A") (pintype "passive"))
      (node (ref "LED66") (pin "A") (pinfunction "A_A") (pintype "passive"))
      (node (ref "LED77") (pin "A") (pinfunction "A_A") (pintype "passive"))
      (node (ref "LED88") (pin "A") (pinfunction "A_A") (pintype "passive"))
      (node (ref "LED99") (pin "A") (pinfunction "A_A") (pintype "passive"))
      (node (ref "U$1") (pin "8") (pinfunction "CS11_8") (pintype "bidirectional"))
    )
    (net (code "14") (name "/IRQ") (class "Default")
      (node (ref "JP4") (pin "1") (pinfunction "1_1") (pintype "passive"))
      (node (ref "U$1") (pin "11") (pinfunction "IRQ_11") (pintype "bidirectional"))
    )
    (net (code "15") (name "/RSTN") (class "Default")
      (node (ref "JP3") (pin "1") (pinfunction "1_1") (pintype "passive"))
      (node (ref "R1") (pin "1") (pinfunction "1_1") (pintype "passive"))
      (node (ref "U$1") (pin "13") (pinfunction "RSTN_13") (pintype "bidirectional"))
    )
    (net (code "16") (name "/SCL") (class "Default")
      (node (ref "JP2") (pin "2") (pinfunction "2_2") (pintype "passive"))
      (node (ref "R3") (pin "1") (pinfunction "1_1") (pintype "passive"))
      (node (ref "U$1") (pin "15") (pinfunction "SCL_15") (pintype "bidirectional"))
    )
    (net (code "17") (name "/SDA") (class "Default")
      (node (ref "JP2") (pin "1") (pinfunction "1_1") (pintype "passive"))
      (node (ref "R2") (pin "1") (pinfunction "1_1") (pintype "passive"))
      (node (ref "U$1") (pin "16") (pinfunction "SDA_16") (pintype "bidirectional"))
    )
    (net (code "18") (name "/SYNC") (class "Default")
      (node (ref "JP5") (pin "1") (pinfunction "1_1") (pintype "passive"))
      (node (ref "U$1") (pin "12") (pinfunction "SYNC_12") (pintype "bidirectional"))
    )
    (net (code "19") (name "GND") (class "Default")
      (node (ref "C1") (pin "2") (pinfunction "2_2") (pintype "passive"))
      (node (ref "JP1") (pin "2") (pinfunction "2_2") (pintype "passive"))
      (node (ref "RADDR") (pin "1") (pinfunction "1_1") (pintype "passive"))
      (node (ref "U$1") (pin "1") (pinfunction "GND_1") (pintype "bidirectional"))
      (node (ref "U$1") (pin "14") (pinfunction "GND_14") (pintype "bidirectional"))
      (node (ref "U$1") (pin "22") (pinfunction "GND_22") (pintype "bidirectional"))
      (node (ref "U$1") (pin "28") (pinfunction "GND_28") (pintype "bidirectional"))
      (node (ref "U$1") (pin "7") (pinfunction "GND_7") (pintype "bidirectional"))
    )
    (net (code "20") (name "Net-(U$1-ADDR)") (class "Default")
      (node (ref "RADDR") (pin "2") (pinfunction "2_2") (pintype "passive"))
      (node (ref "U$1") (pin "17") (pinfunction "ADDR_17") (pintype "bidirectional"))
    )
  )
)
